# VREG_RT9166-25PVL_with_EN.net
KiCad netlist of a schematic drawn in Altium Designer
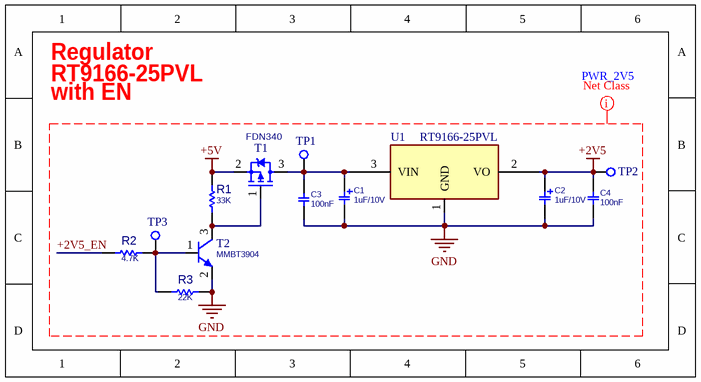
[diagram p0: VREG RT9166-25PVL with EN.SchDoc]

(export (version "E")
  (design (tool "Eeschema 10.0.6"))
  (components
    (comp (ref "C1")
      (value "1uF/10V")
      (footprint "C_TN_A")
      (description "CAP, SMD, TAN")
      (libsource (lib "PW Components 97_492") (part "CAP_SMD_TAN"))
    )
    (comp (ref "C2")
      (value "1uF/10V")
      (footprint "C_TN_A")
      (description "CAP, SMD, TAN")
      (libsource (lib "PW Components 97_492") (part "CAP_SMD_TAN"))
    )
    (comp (ref "C3")
      (value "100nF")
      (footprint "C0603S")
      (description "CAP, SMD, MLCC")
      (fields (field (name "MANF_P#") "MANF_PART#") (field (name "MANF") "Murata"))
      (libsource (lib "Passive") (part "CAP_SMD_MLCC"))
    )
    (comp (ref "C4")
      (value "100nF")
      (footprint "C0603S")
      (description "CAP, SMD, MLCC")
      (fields (field (name "MANF_P#") "MANF_PART#") (field (name "MANF") "Murata"))
      (libsource (lib "Passive") (part "CAP_SMD_MLCC"))
    )
    (comp (ref "R1")
      (value "33K")
      (footprint "R0603S")
      (description "RES, SMD")
      (fields (field (name "MANF_P#") "RK73H1ETTP4701F") (field (name "MANF") "KOA SPEER"))
      (libsource (lib "Passive") (part "RES_SMD"))
    )
    (comp (ref "R2")
      (value "4.7K")
      (footprint "R0603S")
      (description "RES, SMD")
      (fields (field (name "MANF_P#") "RK73H1ETTP4701F") (field (name "MANF") "KOA SPEER"))
      (libsource (lib "Passive") (part "RES_SMD"))
    )
    (comp (ref "R3")
      (value "22K")
      (footprint "R0603S")
      (description "RES, SMD")
      (fields (field (name "MANF_P#") "RK73H1ETTP4701F") (field (name "MANF") "KOA SPEER"))
      (libsource (lib "Passive") (part "RES_SMD"))
    )
    (comp (ref "T1")
      (value "FDN340")
      (footprint "SOT23_3")
      (description "MOSFET SMD P-CH 20V 2A")
      (fields (field (name "MANF_P#") "FDN360"))
      (libsource (lib "Transistor FET") (part "MOSP_FDN340_SOT23"))
    )
    (comp (ref "T2")
      (value "MMBT3904")
      (footprint "SOT23_3")
      (description "BJT, NPN, 40V, 0.2A, SMD, SOT23")
      (fields (field (name "MANF") "Diodes, NXP, FAIRCHILD, ON"))
      (libsource (lib "Transistor BJT") (part "NPN_MMBT3904_SOT23"))
    )
    (comp (ref "TP1")
      (value "Test Point")
      (footprint "TPSMD_C1")
      (libsource (lib "Passives") (part "Test Point"))
    )
    (comp (ref "TP2")
      (value "Test Point")
      (footprint "TPSMD_C1")
      (libsource (lib "Passives") (part "Test Point"))
    )
    (comp (ref "TP3")
      (value "Test Point")
      (footprint "TPSMD_C1")
      (libsource (lib "Passives") (part "Test Point"))
    )
    (comp (ref "U1")
      (value "RT9166-25PVL")
      (footprint "SOT23_3")
      (description "REG, Linear, Fixed, 2.5v, 0.3A/0.6A, SOT23")
      (fields (field (name "MANF") "TI"))
      (libsource (lib "PW Components 97_481") (part "VREG_RT9166A-25PVL_SOT23"))
    )
  )
  (nets
    (net (code "1") (name "+2V5") (class "Default")
      (node (ref "C2") (pin "1") (pinfunction "1_1") (pintype "passive"))
      (node (ref "C4") (pin "1") (pinfunction "1_1") (pintype "passive"))
      (node (ref "TP2") (pin "1") (pinfunction "TP_1") (pintype "passive"))
      (node (ref "U1") (pin "2") (pinfunction "VO_2") (pintype "passive"))
    )
    (net (code "2") (name "+5V") (class "Default")
      (node (ref "R1") (pin "2") (pinfunction "2_2") (pintype "passive"))
      (node (ref "T1") (pin "2") (pinfunction "S_2") (pintype "passive"))
    )
    (net (code "3") (name "/+2V5_EN") (class "Default")
      (node (ref "R2") (pin "2") (pinfunction "2_2") (pintype "passive"))
    )
    (net (code "4") (name "GND") (class "Default")
      (node (ref "C1") (pin "2") (pinfunction "2_2") (pintype "passive"))
      (node (ref "C2") (pin "2") (pinfunction "2_2") (pintype "passive"))
      (node (ref "C3") (pin "2") (pinfunction "2_2") (pintype "passive"))
      (node (ref "C4") (pin "2") (pinfunction "2_2") (pintype "passive"))
      (node (ref "R3") (pin "1") (pinfunction "1_1") (pintype "passive"))
      (node (ref "T2") (pin "2") (pinfunction "E_2") (pintype "passive"))
      (node (ref "U1") (pin "1") (pinfunction "GND_1") (pintype "passive"))
    )
    (net (code "5") (name "Net-(T1-D)") (class "Default")
      (node (ref "C1") (pin "1") (pinfunction "1_1") (pintype "passive"))
      (node (ref "C3") (pin "1") (pinfunction "1_1") (pintype "passive"))
      (node (ref "T1") (pin "3") (pinfunction "D_3") (pintype "passive"))
      (node (ref "TP1") (pin "1") (pinfunction "TP_1") (pintype "passive"))
      (node (ref "U1") (pin "3") (pinfunction "VIN_3") (pintype "passive"))
    )
    (net (code "6") (name "Net-(T1-G)") (class "Default")
      (node (ref "R1") (pin "1") (pinfunction "1_1") (pintype "passive"))
      (node (ref "T1") (pin "1") (pinfunction "G_1") (pintype "passive"))
      (node (ref "T2") (pin "3") (pinfunction "C_3") (pintype "passive"))
    )
    (net (code "7") (name "Net-(T2-B)") (class "Default")
      (node (ref "R2") (pin "1") (pinfunction "1_1") (pintype "passive"))
      (node (ref "R3") (pin "2") (pinfunction "2_2") (pintype "passive"))
      (node (ref "T2") (pin "1") (pinfunction "B_1") (pintype "passive"))
      (node (ref "TP3") (pin "1") (pinfunction "TP_1") (pintype "passive"))
    )
  )
)
